# IMUinator2368.net
KiCad netlist of a schematic drawn in EAGLE
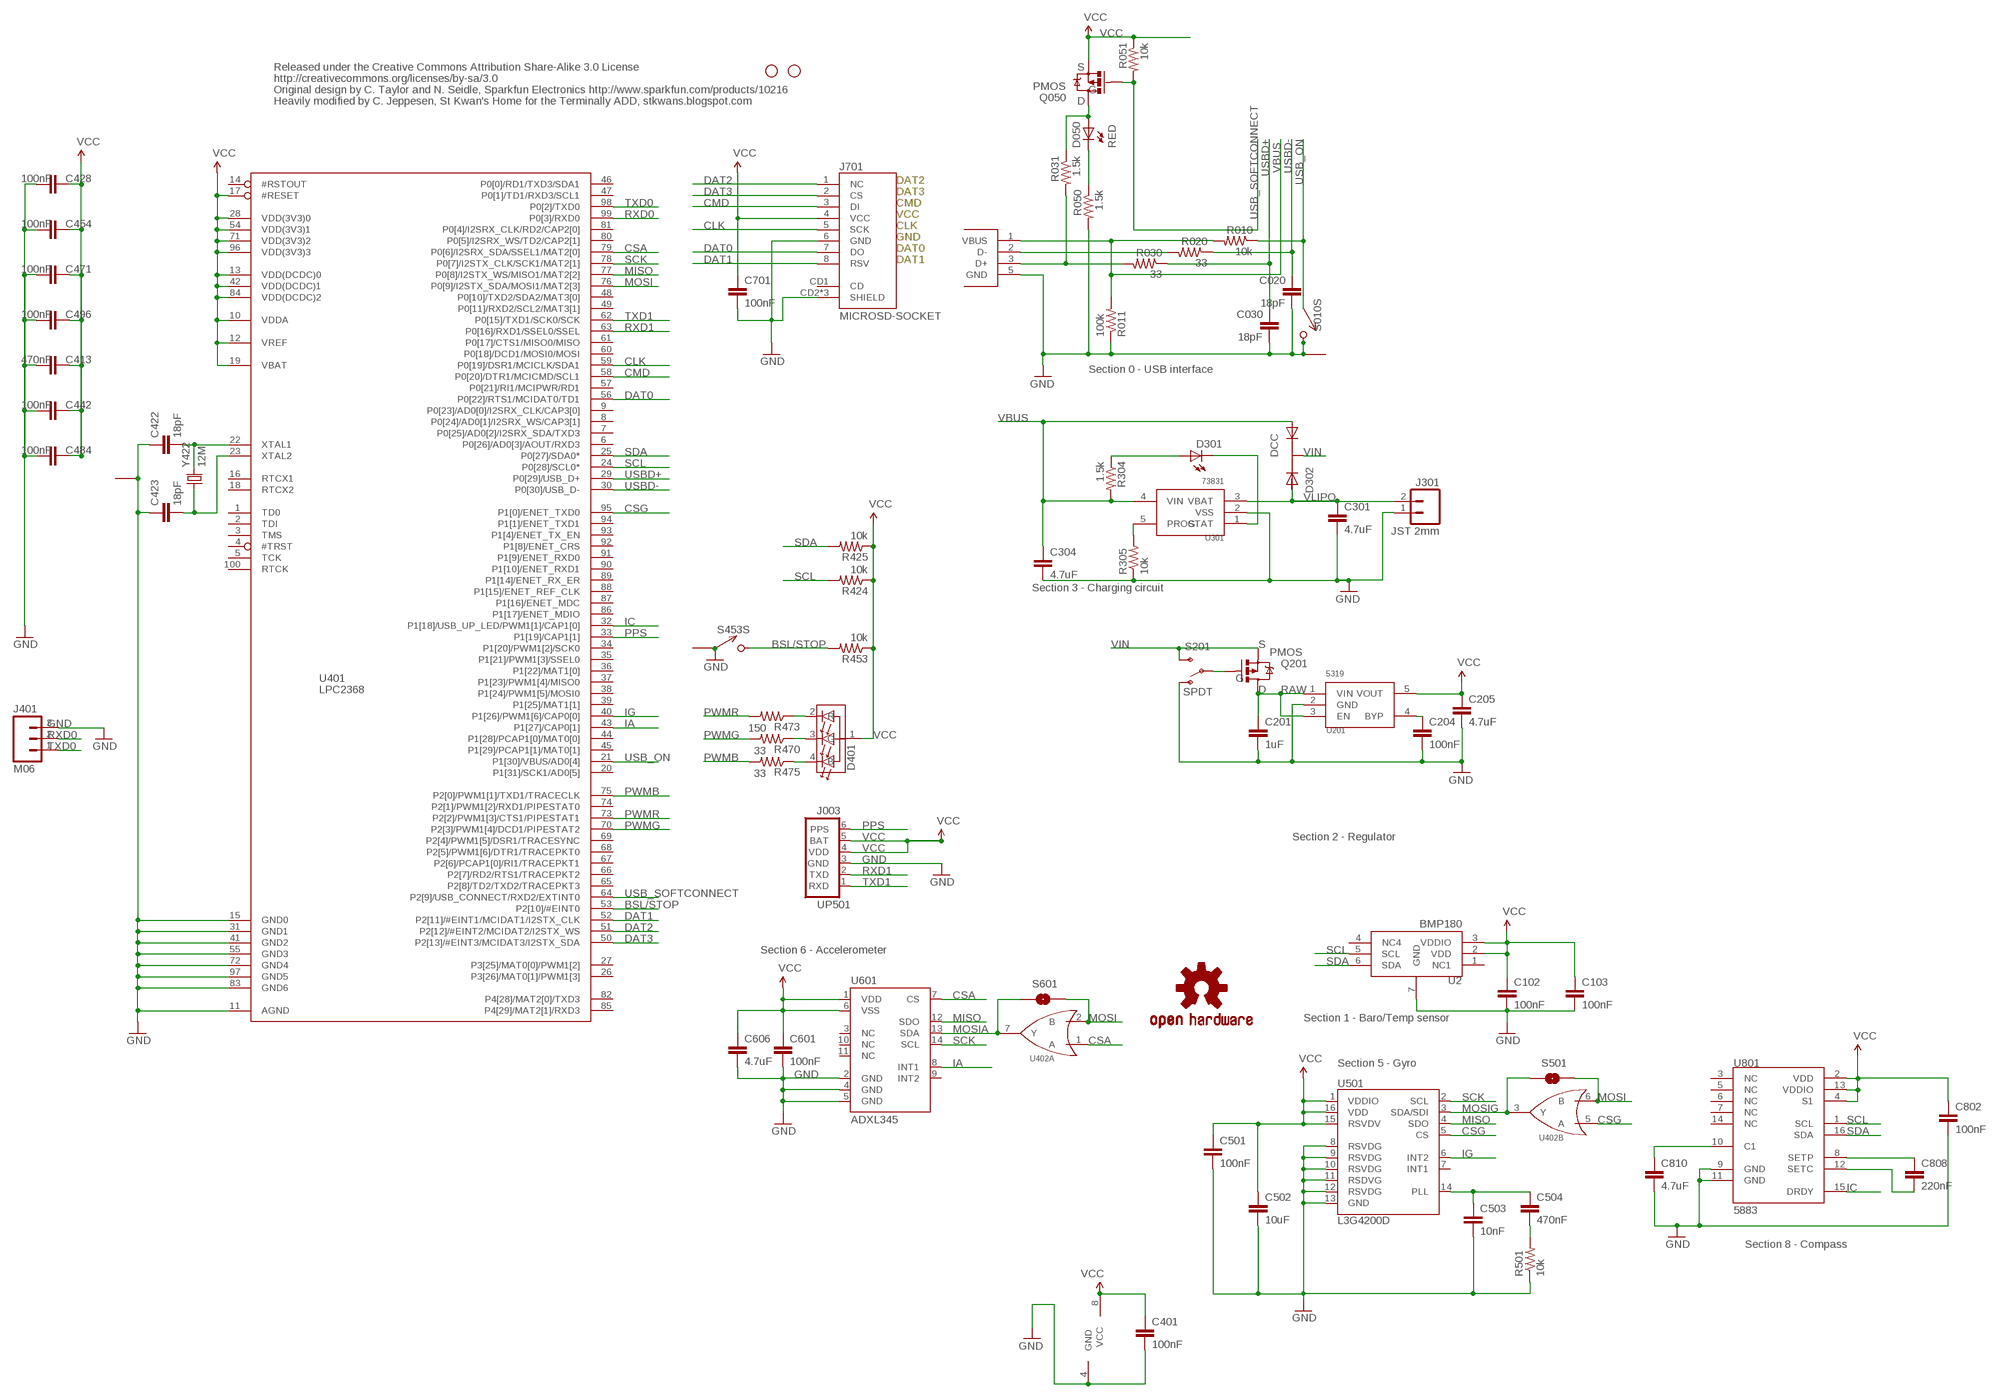
[diagram p0: schematic, sheet 1]

(export (version "E")
  (design (tool "Eeschema 10.0.6"))
  (components
    (comp (ref "C020")
      (value "18pF")
      (footprint "eagle-import:0402-CAP")
      (libsource (lib "eagle-import") (part "CAP0402-CAP"))
    )
    (comp (ref "C030")
      (value "18pF")
      (footprint "eagle-import:0402-CAP")
      (libsource (lib "eagle-import") (part "CAP0402-CAP"))
    )
    (comp (ref "C102")
      (value "100nF")
      (footprint "eagle-import:0402-CAP")
      (libsource (lib "eagle-import") (part "CAP0402-CAP"))
    )
    (comp (ref "C103")
      (value "100nF")
      (footprint "eagle-import:0402-CAP")
      (libsource (lib "eagle-import") (part "CAP0402-CAP"))
    )
    (comp (ref "C201")
      (value "1uF")
      (footprint "eagle-import:0402-CAP")
      (libsource (lib "eagle-import") (part "CAP0402-CAP"))
    )
    (comp (ref "C204")
      (value "100nF")
      (footprint "eagle-import:0402-CAP")
      (libsource (lib "eagle-import") (part "CAP0402-CAP"))
    )
    (comp (ref "C205")
      (value "4.7uF")
      (footprint "eagle-import:0402-CAP")
      (libsource (lib "eagle-import") (part "CAP0402-CAP"))
    )
    (comp (ref "C301")
      (value "4.7uF")
      (footprint "eagle-import:0402-CAP")
      (libsource (lib "eagle-import") (part "CAP0402-CAP"))
    )
    (comp (ref "C304")
      (value "4.7uF")
      (footprint "eagle-import:0402-CAP")
      (libsource (lib "eagle-import") (part "CAP0402-CAP"))
    )
    (comp (ref "C401")
      (value "100nF")
      (footprint "eagle-import:0402-CAP")
      (libsource (lib "eagle-import") (part "CAP0402-CAP"))
    )
    (comp (ref "C413")
      (value "470nF")
      (footprint "eagle-import:0402-CAP")
      (libsource (lib "eagle-import") (part "CAP0402-CAP"))
    )
    (comp (ref "C422")
      (value "18pF")
      (footprint "eagle-import:0402-CAP")
      (libsource (lib "eagle-import") (part "CAP0402-CAP"))
    )
    (comp (ref "C423")
      (value "18pF")
      (footprint "eagle-import:0402-CAP")
      (libsource (lib "eagle-import") (part "CAP0402-CAP"))
    )
    (comp (ref "C428")
      (value "100nF")
      (footprint "eagle-import:0402-CAP")
      (libsource (lib "eagle-import") (part "CAP0402-CAP"))
    )
    (comp (ref "C442")
      (value "100nF")
      (footprint "eagle-import:0402-CAP")
      (libsource (lib "eagle-import") (part "CAP0402-CAP"))
    )
    (comp (ref "C454")
      (value "100nF")
      (footprint "eagle-import:0402-CAP")
      (libsource (lib "eagle-import") (part "CAP0402-CAP"))
    )
    (comp (ref "C471")
      (value "100nF")
      (footprint "eagle-import:0402-CAP")
      (libsource (lib "eagle-import") (part "CAP0402-CAP"))
    )
    (comp (ref "C484")
      (value "100nF")
      (footprint "eagle-import:0402-CAP")
      (libsource (lib "eagle-import") (part "CAP0402-CAP"))
    )
    (comp (ref "C496")
      (value "100nF")
      (footprint "eagle-import:0402-CAP")
      (libsource (lib "eagle-import") (part "CAP0402-CAP"))
    )
    (comp (ref "C501")
      (value "100nF")
      (footprint "eagle-import:0402-CAP")
      (libsource (lib "eagle-import") (part "CAP0402-CAP"))
    )
    (comp (ref "C502")
      (value "10uF")
      (footprint "eagle-import:0603-CAP")
      (libsource (lib "eagle-import") (part "SparkFun-Passives_CAP0603-CAP"))
    )
    (comp (ref "C503")
      (value "10nF")
      (footprint "eagle-import:0402-CAP")
      (libsource (lib "eagle-import") (part "CAP0402-CAP"))
    )
    (comp (ref "C504")
      (value "470nF")
      (footprint "eagle-import:0402-CAP")
      (libsource (lib "eagle-import") (part "CAP0402-CAP"))
    )
    (comp (ref "C601")
      (value "100nF")
      (footprint "eagle-import:0402-CAP")
      (libsource (lib "eagle-import") (part "CAP0402-CAP"))
    )
    (comp (ref "C606")
      (value "4.7uF")
      (footprint "eagle-import:0402-CAP")
      (libsource (lib "eagle-import") (part "CAP0402-CAP"))
    )
    (comp (ref "C701")
      (value "100nF")
      (footprint "eagle-import:0402-CAP")
      (libsource (lib "eagle-import") (part "CAP0402-CAP"))
    )
    (comp (ref "C802")
      (value "100nF")
      (footprint "eagle-import:0402-CAP")
      (libsource (lib "eagle-import") (part "CAP0402-CAP"))
    )
    (comp (ref "C808")
      (value "220nF")
      (footprint "eagle-import:0402-CAP")
      (libsource (lib "eagle-import") (part "CAP0402-CAP"))
    )
    (comp (ref "C810")
      (value "4.7uF")
      (footprint "eagle-import:0402-CAP")
      (libsource (lib "eagle-import") (part "CAP0402-CAP"))
    )
    (comp (ref "D050")
      (value "RED")
      (footprint "eagle-import:LED-0603")
      (libsource (lib "eagle-import") (part "LED0603"))
    )
    (comp (ref "D301")
      (value "RED")
      (footprint "eagle-import:LED-0603")
      (libsource (lib "eagle-import") (part "LED0603"))
    )
    (comp (ref "D302")
      (value "DCC")
      (footprint "eagle-import:SOT-23-3")
      (libsource (lib "eagle-import") (part "PMEG2005CT"))
    )
    (comp (ref "D401")
      (value "RGB")
      (footprint "eagle-import:HSMF-C118")
      (libsource (lib "eagle-import") (part "HSMF-C118"))
    )
    (comp (ref "J001")
      (value "USB_MICROB_JST")
      (footprint "eagle-import:UB-MC5BR3-SD204-4S")
      (libsource (lib "eagle-import") (part "USB_MICROB_JST"))
    )
    (comp (ref "J003")
      (value "UP501")
      (footprint "eagle-import:UP501")
      (libsource (lib "eagle-import") (part "UP501"))
    )
    (comp (ref "J301")
      (value "JST 2mm")
      (footprint "eagle-import:JST-2-SMD")
      (libsource (lib "eagle-import") (part "M02-JST-2MM-SMT"))
    )
    (comp (ref "J401")
      (value "M06")
      (footprint "eagle-import:1X03")
      (libsource (lib "eagle-import") (part "M03PTH"))
    )
    (comp (ref "J701")
      (value "MICROSD-SOCKET")
      (footprint "eagle-import:MICROSD-SOCKET-PP")
      (libsource (lib "eagle-import") (part "MICROSD-SOCKET"))
    )
    (comp (ref "JP1")
      (value "STAND-OFF")
      (footprint "eagle-import:STAND-OFF")
      (libsource (lib "eagle-import") (part "STAND-OFF"))
    )
    (comp (ref "JP2")
      (value "STAND-OFF")
      (footprint "eagle-import:STAND-OFF")
      (libsource (lib "eagle-import") (part "STAND-OFF"))
    )
    (comp (ref "Q050")
      (value "PMOS")
      (footprint "eagle-import:SOT23-3")
      (libsource (lib "eagle-import") (part "MOSFET-PCHANNELSMD"))
    )
    (comp (ref "Q201")
      (value "PMOS")
      (footprint "eagle-import:SOT23-3")
      (libsource (lib "eagle-import") (part "MOSFET-PCHANNELSMD"))
    )
    (comp (ref "R010")
      (value "10k")
      (footprint "eagle-import:0402-RES")
      (libsource (lib "eagle-import") (part "RESISTOR0402-RES"))
    )
    (comp (ref "R011")
      (value "100k")
      (footprint "eagle-import:0402-RES")
      (libsource (lib "eagle-import") (part "RESISTOR0402-RES"))
    )
    (comp (ref "R020")
      (value "33")
      (footprint "eagle-import:0402-RES")
      (libsource (lib "eagle-import") (part "RESISTOR0402-RES"))
    )
    (comp (ref "R030")
      (value "33")
      (footprint "eagle-import:0402-RES")
      (libsource (lib "eagle-import") (part "RESISTOR0402-RES"))
    )
    (comp (ref "R031")
      (value "1.5k")
      (footprint "eagle-import:0402-RES")
      (libsource (lib "eagle-import") (part "RESISTOR0402-RES"))
    )
    (comp (ref "R050")
      (value "1.5k")
      (footprint "eagle-import:0402-RES")
      (libsource (lib "eagle-import") (part "RESISTOR0402-RES"))
    )
    (comp (ref "R051")
      (value "10k")
      (footprint "eagle-import:0402-RES")
      (libsource (lib "eagle-import") (part "RESISTOR0402-RES"))
    )
    (comp (ref "R304")
      (value "1.5k")
      (footprint "eagle-import:0402-RES")
      (libsource (lib "eagle-import") (part "RESISTOR0402-RES"))
    )
    (comp (ref "R305")
      (value "10k")
      (footprint "eagle-import:0402-RES")
      (libsource (lib "eagle-import") (part "RESISTOR0402-RES"))
    )
    (comp (ref "R424")
      (value "10k")
      (footprint "eagle-import:0402-RES")
      (libsource (lib "eagle-import") (part "SparkFun-Passives_RESISTOR0402-RES"))
    )
    (comp (ref "R425")
      (value "10k")
      (footprint "eagle-import:0402-RES")
      (libsource (lib "eagle-import") (part "SparkFun-Passives_RESISTOR0402-RES"))
    )
    (comp (ref "R453")
      (value "10k")
      (footprint "eagle-import:0402-RES")
      (libsource (lib "eagle-import") (part "SparkFun-Passives_RESISTOR0402-RES"))
    )
    (comp (ref "R470")
      (value "33")
      (footprint "eagle-import:0402-RES")
      (libsource (lib "eagle-import") (part "RESISTOR0402-RES"))
    )
    (comp (ref "R473")
      (value "150")
      (footprint "eagle-import:0402-RES")
      (libsource (lib "eagle-import") (part "RESISTOR0402-RES"))
    )
    (comp (ref "R475")
      (value "33")
      (footprint "eagle-import:0402-RES")
      (libsource (lib "eagle-import") (part "RESISTOR0402-RES"))
    )
    (comp (ref "R501")
      (value "10k")
      (footprint "eagle-import:0402-RES")
      (libsource (lib "eagle-import") (part "SparkFun-Passives_RESISTOR0402-RES"))
    )
    (comp (ref "S010")
      (value "SPST")
      (footprint "eagle-import:B3U-1100P")
      (fields (field (name "DIGIKEY") "SW1021CT-ND"))
      (libsource (lib "eagle-import") (part "B3U-1100P"))
    )
    (comp (ref "S201")
      (value "SPDT")
      (footprint "eagle-import:AYZ0202")
      (libsource (lib "eagle-import") (part "SWITCH-SPSTSMD"))
    )
    (comp (ref "S453")
      (value "SPST")
      (footprint "eagle-import:B3U-1100P")
      (fields (field (name "DIGIKEY") "SW1021CT-ND"))
      (libsource (lib "eagle-import") (part "B3U-1100P"))
    )
    (comp (ref "S501")
      (value "SOLDERJUMPERNO")
      (footprint "eagle-import:SJ_2S-NO")
      (libsource (lib "eagle-import") (part "SOLDERJUMPERNO"))
    )
    (comp (ref "S601")
      (value "SOLDERJUMPERNO")
      (footprint "eagle-import:SJ_2S-NO")
      (libsource (lib "eagle-import") (part "SOLDERJUMPERNO"))
    )
    (comp (ref "U$3")
      (value "OSHW-LOGOS")
      (footprint "eagle-import:OSHW-LOGO-S")
      (libsource (lib "eagle-import") (part "OSHW-LOGOS"))
    )
    (comp (ref "U2")
      (value "BMP180")
      (footprint "eagle-import:BMP180")
      (libsource (lib "eagle-import") (part "BMP180"))
    )
    (comp (ref "U201")
      (value "5319")
      (footprint "eagle-import:SOT-23-5")
      (libsource (lib "eagle-import") (part "MIC5319D5"))
    )
    (comp (ref "U301")
      (value "73831")
      (footprint "eagle-import:SOT-23-5")
      (libsource (lib "eagle-import") (part "MCP73831"))
    )
    (comp (ref "U401")
      (value "LPC2368")
      (footprint "eagle-import:LQFP100")
      (libsource (lib "eagle-import") (part "LPC2368"))
    )
    (comp (ref "U402")
      (value "7432")
      (footprint "eagle-import:DCU_8")
      (fields (field (name "DIGIKEY") "296-13268-1-ND"))
      (libsource (lib "eagle-import") (part "SN74LVC2G32"))
    )
    (comp (ref "U501")
      (value "L3G4200D")
      (footprint "eagle-import:LGA16-4X4")
      (libsource (lib "eagle-import") (part "L3G4200D"))
    )
    (comp (ref "U601")
      (value "ADXL345")
      (footprint "eagle-import:LGA14")
      (libsource (lib "eagle-import") (part "ADXL345"))
    )
    (comp (ref "U801")
      (value "5883")
      (footprint "eagle-import:16LPCC")
      (libsource (lib "eagle-import") (part "HMC5883LSMD"))
    )
    (comp (ref "Y422")
      (value "12M")
      (footprint "eagle-import:CRYSTAL_SMD")
      (fields (field (name "DIGIKEY") "887-1316-1-ND"))
      (libsource (lib "eagle-import") (part "TSX-3225"))
    )
  )
  (nets
    (net (code "1") (name "/BSL{slash}STOP") (class "Default")
      (node (ref "R453") (pin "2") (pinfunction "2_2") (pintype "passive"))
      (node (ref "S453") (pin "P$2") (pinfunction "2_P$2") (pintype "bidirectional"))
      (node (ref "U401") (pin "53") (pinfunction "P2[10]/#EINT0_53") (pintype "bidirectional"))
    )
    (net (code "2") (name "/CLK") (class "Default")
      (node (ref "J701") (pin "5") (pinfunction "SCK_5") (pintype "bidirectional"))
      (node (ref "U401") (pin "59") (pinfunction "P0[19]/DSR1/MCICLK/SDA1_59") (pintype "bidirectional"))
    )
    (net (code "3") (name "/CMD") (class "Default")
      (node (ref "J701") (pin "3") (pinfunction "DI_3") (pintype "bidirectional"))
      (node (ref "U401") (pin "58") (pinfunction "P0[20]/DTR1/MCICMD/SCL1_58") (pintype "bidirectional"))
    )
    (net (code "4") (name "/CSA") (class "Default")
      (node (ref "U401") (pin "79") (pinfunction "P0[6]/I2SRX_SDA/SSEL1/MAT2[0]_79") (pintype "bidirectional"))
      (node (ref "U402") (pin "1") (pinfunction "A_1") (pintype "bidirectional"))
      (node (ref "U601") (pin "7") (pinfunction "CS_7") (pintype "bidirectional"))
    )
    (net (code "5") (name "/CSG") (class "Default")
      (node (ref "U401") (pin "95") (pinfunction "P1[0]/ENET_TXD0_95") (pintype "bidirectional"))
      (node (ref "U402") (pin "5") (pinfunction "A_5") (pintype "bidirectional"))
      (node (ref "U501") (pin "5") (pinfunction "CS_5") (pintype "bidirectional"))
    )
    (net (code "6") (name "/DAT0") (class "Default")
      (node (ref "J701") (pin "7") (pinfunction "DO_7") (pintype "bidirectional"))
      (node (ref "U401") (pin "56") (pinfunction "P0[22]/RTS1/MCIDAT0/TD1_56") (pintype "bidirectional"))
    )
    (net (code "7") (name "/DAT1") (class "Default")
      (node (ref "J701") (pin "8") (pinfunction "RSV_8") (pintype "bidirectional"))
      (node (ref "U401") (pin "52") (pinfunction "P2[11]/#EINT1/MCIDAT1/I2STX_CLK_52") (pintype "bidirectional"))
    )
    (net (code "8") (name "/DAT2") (class "Default")
      (node (ref "J701") (pin "1") (pinfunction "NC_1") (pintype "bidirectional"))
      (node (ref "U401") (pin "51") (pinfunction "P2[12]/#EINT2/MCIDAT2/I2STX_WS_51") (pintype "bidirectional"))
    )
    (net (code "9") (name "/DAT3") (class "Default")
      (node (ref "J701") (pin "2") (pinfunction "CS_2") (pintype "bidirectional"))
      (node (ref "U401") (pin "50") (pinfunction "P2[13]/#EINT3/MCIDAT3/I2STX_SDA_50") (pintype "bidirectional"))
    )
    (net (code "10") (name "/IA") (class "Default")
      (node (ref "U401") (pin "43") (pinfunction "P1[27]/CAP0[1]_43") (pintype "bidirectional"))
      (node (ref "U601") (pin "8") (pinfunction "INT1_8") (pintype "bidirectional"))
    )
    (net (code "11") (name "/IC") (class "Default")
      (node (ref "U401") (pin "32") (pinfunction "P1[18]/USB_UP_LED/PWM1[1]/CAP1[0]_32") (pintype "bidirectional"))
      (node (ref "U801") (pin "15") (pinfunction "DRDY_15") (pintype "bidirectional"))
    )
    (net (code "12") (name "/IG") (class "Default")
      (node (ref "U401") (pin "40") (pinfunction "P1[26]/PWM1[6]/CAP0[0]_40") (pintype "bidirectional"))
      (node (ref "U501") (pin "6") (pinfunction "INT2_6") (pintype "bidirectional"))
    )
    (net (code "13") (name "/MISO") (class "Default")
      (node (ref "U401") (pin "77") (pinfunction "P0[8]/I2STX_WS/MISO1/MAT2[2]_77") (pintype "bidirectional"))
      (node (ref "U501") (pin "4") (pinfunction "SDO_4") (pintype "bidirectional"))
      (node (ref "U601") (pin "12") (pinfunction "SDO_12") (pintype "bidirectional"))
    )
    (net (code "14") (name "/MOSI") (class "Default")
      (node (ref "S501") (pin "2") (pinfunction "2_2") (pintype "passive"))
      (node (ref "S601") (pin "2") (pinfunction "2_2") (pintype "passive"))
      (node (ref "U401") (pin "76") (pinfunction "P0[9]/I2STX_SDA/MOSI1/MAT2[3]_76") (pintype "bidirectional"))
      (node (ref "U402") (pin "2") (pinfunction "B_2") (pintype "bidirectional"))
      (node (ref "U402") (pin "6") (pinfunction "B_6") (pintype "bidirectional"))
    )
    (net (code "15") (name "/MOSIA") (class "Default")
      (node (ref "S601") (pin "1") (pinfunction "1_1") (pintype "passive"))
      (node (ref "U402") (pin "7") (pinfunction "Y_7") (pintype "bidirectional"))
      (node (ref "U601") (pin "13") (pinfunction "SDA_13") (pintype "bidirectional"))
    )
    (net (code "16") (name "/MOSIG") (class "Default")
      (node (ref "S501") (pin "1") (pinfunction "1_1") (pintype "passive"))
      (node (ref "U402") (pin "3") (pinfunction "Y_3") (pintype "bidirectional"))
      (node (ref "U501") (pin "3") (pinfunction "SDA/SDI_3") (pintype "bidirectional"))
    )
    (net (code "17") (name "/PPS") (class "Default")
      (node (ref "J003") (pin "6") (pinfunction "PPS_6") (pintype "passive"))
      (node (ref "U401") (pin "33") (pinfunction "P1[19]/CAP1[1]_33") (pintype "bidirectional"))
    )
    (net (code "18") (name "/PWMB") (class "Default")
      (node (ref "R475") (pin "2") (pinfunction "2_2") (pintype "passive"))
      (node (ref "U401") (pin "75") (pinfunction "P2[0]/PWM1[1]/TXD1/TRACECLK_75") (pintype "bidirectional"))
    )
    (net (code "19") (name "/PWMG") (class "Default")
      (node (ref "R470") (pin "2") (pinfunction "2_2") (pintype "passive"))
      (node (ref "U401") (pin "70") (pinfunction "P2[3]/PWM1[4]/DCD1/PIPESTAT2_70") (pintype "bidirectional"))
    )
    (net (code "20") (name "/PWMR") (class "Default")
      (node (ref "R473") (pin "2") (pinfunction "2_2") (pintype "passive"))
      (node (ref "U401") (pin "73") (pinfunction "P2[2]/PWM1[3]/CTS1/PIPESTAT1_73") (pintype "bidirectional"))
    )
    (net (code "21") (name "/RAW") (class "Default")
      (node (ref "C201") (pin "1") (pinfunction "1_1") (pintype "passive"))
      (node (ref "Q201") (pin "3") (pinfunction "D_3") (pintype "passive"))
      (node (ref "U201") (pin "1") (pinfunction "VIN_1") (pintype "bidirectional"))
      (node (ref "U201") (pin "3") (pinfunction "EN_3") (pintype "bidirectional"))
    )
    (net (code "22") (name "/RXD0") (class "Default")
      (node (ref "J401") (pin "2") (pinfunction "2_2") (pintype "passive"))
      (node (ref "U401") (pin "99") (pinfunction "P0[3]/RXD0_99") (pintype "bidirectional"))
    )
    (net (code "23") (name "/RXD1") (class "Default")
      (node (ref "J003") (pin "2") (pinfunction "TXD_2") (pintype "passive"))
      (node (ref "U401") (pin "63") (pinfunction "P0[16]/RXD1/SSEL0/SSEL_63") (pintype "bidirectional"))
    )
    (net (code "24") (name "/SCK") (class "Default")
      (node (ref "U401") (pin "78") (pinfunction "P0[7]/I2STX_CLK/SCK1/MAT2[1]_78") (pintype "bidirectional"))
      (node (ref "U501") (pin "2") (pinfunction "SCL_2") (pintype "bidirectional"))
      (node (ref "U601") (pin "14") (pinfunction "SCL_14") (pintype "bidirectional"))
    )
    (net (code "25") (name "/SCL") (class "Default")
      (node (ref "R424") (pin "2") (pinfunction "2_2") (pintype "passive"))
      (node (ref "U2") (pin "5") (pinfunction "SCL_5") (pintype "input"))
      (node (ref "U401") (pin "24") (pinfunction "P0[28]/SCL0*_24") (pintype "bidirectional"))
      (node (ref "U801") (pin "1") (pinfunction "SCL_1") (pintype "bidirectional"))
    )
    (net (code "26") (name "/SDA") (class "Default")
      (node (ref "R425") (pin "2") (pinfunction "2_2") (pintype "passive"))
      (node (ref "U2") (pin "6") (pinfunction "SDA_6") (pintype "bidirectional"))
      (node (ref "U401") (pin "25") (pinfunction "P0[27]/SDA0*_25") (pintype "bidirectional"))
      (node (ref "U801") (pin "16") (pinfunction "SDA_16") (pintype "bidirectional"))
    )
    (net (code "27") (name "/TXD0") (class "Default")
      (node (ref "J401") (pin "1") (pinfunction "1_1") (pintype "passive"))
      (node (ref "U401") (pin "98") (pinfunction "P0[2]/TXD0_98") (pintype "bidirectional"))
    )
    (net (code "28") (name "/TXD1") (class "Default")
      (node (ref "J003") (pin "1") (pinfunction "RXD_1") (pintype "passive"))
      (node (ref "U401") (pin "62") (pinfunction "P0[15]/TXD1/SCK0/SCK_62") (pintype "bidirectional"))
    )
    (net (code "29") (name "/USBD+") (class "Default")
      (node (ref "C030") (pin "1") (pinfunction "1_1") (pintype "passive"))
      (node (ref "R030") (pin "1") (pinfunction "1_1") (pintype "passive"))
      (node (ref "U401") (pin "29") (pinfunction "P0[29]/USB_D+_29") (pintype "bidirectional"))
    )
    (net (code "30") (name "/USBD-") (class "Default")
      (node (ref "C020") (pin "1") (pinfunction "1_1") (pintype "passive"))
      (node (ref "R020") (pin "1") (pinfunction "1_1") (pintype "passive"))
      (node (ref "U401") (pin "30") (pinfunction "P0[30]/USB_D-_30") (pintype "bidirectional"))
    )
    (net (code "31") (name "/USB_ON") (class "Default")
      (node (ref "R010") (pin "1") (pinfunction "1_1") (pintype "passive"))
      (node (ref "S010") (pin "P$1") (pinfunction "1_P$1") (pintype "bidirectional"))
      (node (ref "U401") (pin "21") (pinfunction "P1[30]/VBUS/AD0[4]_21") (pintype "bidirectional"))
    )
    (net (code "32") (name "/USB_SOFTCONNECT") (class "Default")
      (node (ref "Q050") (pin "1") (pinfunction "G_1") (pintype "passive"))
      (node (ref "R051") (pin "2") (pinfunction "2_2") (pintype "passive"))
      (node (ref "U401") (pin "64") (pinfunction "P2[9]/USB_CONNECT/RXD2/EXTINT0_64") (pintype "bidirectional"))
    )
    (net (code "33") (name "/VBUS") (class "Default")
      (node (ref "C304") (pin "1") (pinfunction "1_1") (pintype "passive"))
      (node (ref "D302") (pin "1") (pinfunction "A1_1") (pintype "passive"))
      (node (ref "J001") (pin "1") (pinfunction "VBUS_1") (pintype "bidirectional"))
      (node (ref "R010") (pin "2") (pinfunction "2_2") (pintype "passive"))
      (node (ref "R011") (pin "2") (pinfunction "2_2") (pintype "passive"))
      (node (ref "R304") (pin "2") (pinfunction "2_2") (pintype "passive"))
      (node (ref "U301") (pin "4") (pinfunction "VIN_4") (pintype "bidirectional"))
    )
    (net (code "34") (name "/VIN") (class "Default")
      (node (ref "D302") (pin "3") (pinfunction "K_3") (pintype "passive"))
      (node (ref "Q201") (pin "2") (pinfunction "S_2") (pintype "passive"))
      (node (ref "S201") (pin "3") (pinfunction "S_3") (pintype "passive"))
    )
    (net (code "35") (name "/VLIPO") (class "Default")
      (node (ref "C301") (pin "1") (pinfunction "1_1") (pintype "passive"))
      (node (ref "D302") (pin "2") (pinfunction "A2_2") (pintype "passive"))
      (node (ref "J301") (pin "2") (pinfunction "2_2") (pintype "passive"))
      (node (ref "U301") (pin "3") (pinfunction "VBAT_3") (pintype "bidirectional"))
    )
    (net (code "36") (name "GND") (class "Default")
      (node (ref "C020") (pin "2") (pinfunction "2_2") (pintype "passive"))
      (node (ref "C030") (pin "2") (pinfunction "2_2") (pintype "passive"))
      (node (ref "C102") (pin "2") (pinfunction "2_2") (pintype "passive"))
      (node (ref "C103") (pin "2") (pinfunction "2_2") (pintype "passive"))
      (node (ref "C201") (pin "2") (pinfunction "2_2") (pintype "passive"))
      (node (ref "C204") (pin "2") (pinfunction "2_2") (pintype "passive"))
      (node (ref "C205") (pin "2") (pinfunction "2_2") (pintype "passive"))
      (node (ref "C301") (pin "2") (pinfunction "2_2") (pintype "passive"))
      (node (ref "C304") (pin "2") (pinfunction "2_2") (pintype "passive"))
      (node (ref "C401") (pin "2") (pinfunction "2_2") (pintype "passive"))
      (node (ref "C413") (pin "2") (pinfunction "2_2") (pintype "passive"))
      (node (ref "C422") (pin "1") (pinfunction "1_1") (pintype "passive"))
      (node (ref "C423") (pin "1") (pinfunction "1_1") (pintype "passive"))
      (node (ref "C428") (pin "2") (pinfunction "2_2") (pintype "passive"))
      (node (ref "C442") (pin "2") (pinfunction "2_2") (pintype "passive"))
      (node (ref "C454") (pin "2") (pinfunction "2_2") (pintype "passive"))
      (node (ref "C471") (pin "2") (pinfunction "2_2") (pintype "passive"))
      (node (ref "C484") (pin "2") (pinfunction "2_2") (pintype "passive"))
      (node (ref "C496") (pin "2") (pinfunction "2_2") (pintype "passive"))
      (node (ref "C501") (pin "2") (pinfunction "2_2") (pintype "passive"))
      (node (ref "C502") (pin "2") (pinfunction "2_2") (pintype "passive"))
      (node (ref "C503") (pin "2") (pinfunction "2_2") (pintype "passive"))
      (node (ref "C601") (pin "2") (pinfunction "2_2") (pintype "passive"))
      (node (ref "C606") (pin "2") (pinfunction "2_2") (pintype "passive"))
      (node (ref "C701") (pin "2") (pinfunction "2_2") (pintype "passive"))
      (node (ref "C802") (pin "2") (pinfunction "2_2") (pintype "passive"))
      (node (ref "C810") (pin "2") (pinfunction "2_2") (pintype "passive"))
      (node (ref "J001") (pin "5") (pinfunction "GND_5") (pintype "bidirectional"))
      (node (ref "J003") (pin "3") (pinfunction "GND_3") (pintype "passive"))
      (node (ref "J301") (pin "1") (pinfunction "1_1") (pintype "passive"))
      (node (ref "J401") (pin "3") (pinfunction "3_3") (pintype "passive"))
      (node (ref "J701") (pin "6") (pinfunction "GND_6") (pintype "bidirectional"))
      (node (ref "J701") (pin "CD2") (pinfunction "SHIELD_CD2") (pintype "bidirectional"))
      (node (ref "J701") (pin "GND1") (pinfunction "SHIELD_GND1") (pintype "bidirectional"))
      (node (ref "J701") (pin "GND3") (pinfunction "SHIELD_GND3") (pintype "bidirectional"))
      (node (ref "R011") (pin "1") (pinfunction "1_1") (pintype "passive"))
      (node (ref "R050") (pin "2") (pinfunction "2_2") (pintype "passive"))
      (node (ref "R305") (pin "1") (pinfunction "1_1") (pintype "passive"))
      (node (ref "R501") (pin "1") (pinfunction "1_1") (pintype "passive"))
      (node (ref "S010") (pin "P$2") (pinfunction "2_P$2") (pintype "bidirectional"))
      (node (ref "S010") (pin "P$3") (pinfunction "1_P$3") (pintype "bidirectional"))
      (node (ref "S201") (pin "1") (pinfunction "O_1") (pintype "passive"))
      (node (ref "S453") (pin "P$1") (pinfunction "1_P$1") (pintype "bidirectional"))
      (node (ref "S453") (pin "P$3") (pinfunction "1_P$3") (pintype "bidirectional"))
      (node (ref "U2") (pin "7") (pinfunction "GND_7") (pintype "power_in"))
      (node (ref "U201") (pin "2") (pinfunction "GND_2") (pintype "bidirectional"))
      (node (ref "U301") (pin "2") (pinfunction "VSS_2") (pintype "bidirectional"))
      (node (ref "U401") (pin "11") (pinfunction "AGND_11") (pintype "bidirectional"))
      (node (ref "U401") (pin "15") (pinfunction "GND0_15") (pintype "bidirectional"))
      (node (ref "U401") (pin "31") (pinfunction "GND1_31") (pintype "bidirectional"))
      (node (ref "U401") (pin "41") (pinfunction "GND2_41") (pintype "bidirectional"))
      (node (ref "U401") (pin "55") (pinfunction "GND3_55") (pintype "bidirectional"))
      (node (ref "U401") (pin "72") (pinfunction "GND4_72") (pintype "bidirectional"))
      (node (ref "U401") (pin "83") (pinfunction "GND6_83") (pintype "bidirectional"))
      (node (ref "U401") (pin "97") (pinfunction "GND5_97") (pintype "bidirectional"))
      (node (ref "U402") (pin "4") (pinfunction "GND_4") (pintype "bidirectional"))
      (node (ref "U501") (pin "10") (pinfunction "RSVDG_10") (pintype "bidirectional"))
      (node (ref "U501") (pin "11") (pinfunction "RSDVG_11") (pintype "bidirectional"))
      (node (ref "U501") (pin "12") (pinfunction "RSVDG_12") (pintype "bidirectional"))
      (node (ref "U501") (pin "13") (pinfunction "GND_13") (pintype "bidirectional"))
      (node (ref "U501") (pin "8") (pinfunction "RSVDG_8") (pintype "bidirectional"))
      (node (ref "U501") (pin "9") (pinfunction "RSVDG_9") (pintype "bidirectional"))
      (node (ref "U601") (pin "2") (pinfunction "GND_2") (pintype "bidirectional"))
      (node (ref "U601") (pin "4") (pinfunction "GND_4") (pintype "bidirectional"))
      (node (ref "U601") (pin "5") (pinfunction "GND_5") (pintype "bidirectional"))
      (node (ref "U801") (pin "11") (pinfunction "GND_11") (pintype "bidirectional"))
      (node (ref "U801") (pin "9") (pinfunction "GND_9") (pintype "bidirectional"))
      (node (ref "Y422") (pin "2") (pinfunction "1_2") (pintype "bidirectional"))
    )
    (net (code "37") (name "Net-(C504-Pad2)") (class "Default")
      (node (ref "C504") (pin "2") (pinfunction "2_2") (pintype "passive"))
      (node (ref "R501") (pin "2") (pinfunction "2_2") (pintype "passive"))
    )
    (net (code "38") (name "Net-(D050-PadC)") (class "Default")
      (node (ref "D050") (pin "C") (pinfunction "C_C") (pintype "passive"))
      (node (ref "R050") (pin "1") (pinfunction "1_1") (pintype "passive"))
    )
    (net (code "39") (name "Net-(D301-PadA)") (class "Default")
      (node (ref "D301") (pin "A") (pinfunction "A_A") (pintype "passive"))
      (node (ref "R304") (pin "1") (pinfunction "1_1") (pintype "passive"))
    )
    (net (code "40") (name "Net-(D401-B)") (class "Default")
      (node (ref "D401") (pin "4") (pinfunction "B_4") (pintype "passive"))
      (node (ref "R475") (pin "1") (pinfunction "1_1") (pintype "passive"))
    )
    (net (code "41") (name "Net-(D401-G)") (class "Default")
      (node (ref "D401") (pin "3") (pinfunction "G_3") (pintype "passive"))
      (node (ref "R470") (pin "1") (pinfunction "1_1") (pintype "passive"))
    )
    (net (code "42") (name "Net-(D401-R)") (class "Default")
      (node (ref "D401") (pin "2") (pinfunction "R_2") (pintype "passive"))
      (node (ref "R473") (pin "1") (pinfunction "1_1") (pintype "passive"))
    )
    (net (code "43") (name "Net-(J001-D+)") (class "Default")
      (node (ref "J001") (pin "3") (pinfunction "D+_3") (pintype "bidirectional"))
      (node (ref "R030") (pin "2") (pinfunction "2_2") (pintype "passive"))
      (node (ref "R031") (pin "2") (pinfunction "2_2") (pintype "passive"))
    )
    (net (code "44") (name "Net-(J001-D-)") (class "Default")
      (node (ref "J001") (pin "2") (pinfunction "D-_2") (pintype "bidirectional"))
      (node (ref "R020") (pin "2") (pinfunction "2_2") (pintype "passive"))
    )
    (net (code "45") (name "Net-(Q050-D)") (class "Default")
      (node (ref "D050") (pin "A") (pinfunction "A_A") (pintype "passive"))
      (node (ref "Q050") (pin "3") (pinfunction "D_3") (pintype "passive"))
      (node (ref "R031") (pin "1") (pinfunction "1_1") (pintype "passive"))
    )
    (net (code "46") (name "Net-(Q201-G)") (class "Default")
      (node (ref "Q201") (pin "1") (pinfunction "G_1") (pintype "passive"))
      (node (ref "S201") (pin "2") (pinfunction "P_2") (pintype "passive"))
    )
    (net (code "47") (name "Net-(U201-BYP)") (class "Default")
      (node (ref "C204") (pin "1") (pinfunction "1_1") (pintype "passive"))
      (node (ref "U201") (pin "4") (pinfunction "BYP_4") (pintype "bidirectional"))
    )
    (net (code "48") (name "Net-(U301-PROG)") (class "Default")
      (node (ref "R305") (pin "2") (pinfunction "2_2") (pintype "passive"))
      (node (ref "U301") (pin "5") (pinfunction "PROG_5") (pintype "bidirectional"))
    )
    (net (code "49") (name "Net-(U301-STAT)") (class "Default")
      (node (ref "D301") (pin "C") (pinfunction "C_C") (pintype "passive"))
      (node (ref "U301") (pin "1") (pinfunction "STAT_1") (pintype "bidirectional"))
    )
    (net (code "50") (name "Net-(U401-XTAL1)") (class "Default")
      (node (ref "C422") (pin "2") (pinfunction "2_2") (pintype "passive"))
      (node (ref "U401") (pin "22") (pinfunction "XTAL1_22") (pintype "bidirectional"))
      (node (ref "Y422") (pin "3") (pinfunction "2_3") (pintype "passive"))
    )
    (net (code "51") (name "Net-(U401-XTAL2)") (class "Default")
      (node (ref "C423") (pin "2") (pinfunction "2_2") (pintype "passive"))
      (node (ref "U401") (pin "23") (pinfunction "XTAL2_23") (pintype "bidirectional"))
      (node (ref "Y422") (pin "1") (pinfunction "1_1") (pintype "passive"))
    )
    (net (code "52") (name "Net-(U501-PLL)") (class "Default")
      (node (ref "C503") (pin "1") (pinfunction "1_1") (pintype "passive"))
      (node (ref "C504") (pin "1") (pinfunction "1_1") (pintype "passive"))
      (node (ref "U501") (pin "14") (pinfunction "PLL_14") (pintype "bidirectional"))
    )
    (net (code "53") (name "Net-(U801-C1)") (class "Default")
      (node (ref "C810") (pin "1") (pinfunction "1_1") (pintype "passive"))
      (node (ref "U801") (pin "10") (pinfunction "C1_10") (pintype "bidirectional"))
    )
    (net (code "54") (name "Net-(U801-SETC)") (class "Default")
      (node (ref "C808") (pin "2") (pinfunction "2_2") (pintype "passive"))
      (node (ref "U801") (pin "12") (pinfunction "SETC_12") (pintype "bidirectional"))
    )
    (net (code "55") (name "Net-(U801-SETP)") (class "Default")
      (node (ref "C808") (pin "1") (pinfunction "1_1") (pintype "passive"))
      (node (ref "U801") (pin "8") (pinfunction "SETP_8") (pintype "bidirectional"))
    )
    (net (code "56") (name "VCC") (class "Default")
      (node (ref "C102") (pin "1") (pinfunction "1_1") (pintype "passive"))
      (node (ref "C103") (pin "1") (pinfunction "1_1") (pintype "passive"))
      (node (ref "C205") (pin "1") (pinfunction "1_1") (pintype "passive"))
      (node (ref "C401") (pin "1") (pinfunction "1_1") (pintype "passive"))
      (node (ref "C413") (pin "1") (pinfunction "1_1") (pintype "passive"))
      (node (ref "C428") (pin "1") (pinfunction "1_1") (pintype "passive"))
      (node (ref "C442") (pin "1") (pinfunction "1_1") (pintype "passive"))
      (node (ref "C454") (pin "1") (pinfunction "1_1") (pintype "passive"))
      (node (ref "C471") (pin "1") (pinfunction "1_1") (pintype "passive"))
      (node (ref "C484") (pin "1") (pinfunction "1_1") (pintype "passive"))
      (node (ref "C496") (pin "1") (pinfunction "1_1") (pintype "passive"))
      (node (ref "C501") (pin "1") (pinfunction "1_1") (pintype "passive"))
      (node (ref "C502") (pin "1") (pinfunction "1_1") (pintype "passive"))
      (node (ref "C601") (pin "1") (pinfunction "1_1") (pintype "passive"))
      (node (ref "C606") (pin "1") (pinfunction "1_1") (pintype "passive"))
      (node (ref "C701") (pin "1") (pinfunction "1_1") (pintype "passive"))
      (node (ref "C802") (pin "1") (pinfunction "1_1") (pintype "passive"))
      (node (ref "D401") (pin "1") (pinfunction "A_1") (pintype "passive"))
      (node (ref "J003") (pin "4") (pinfunction "VDD_4") (pintype "passive"))
      (node (ref "J003") (pin "5") (pinfunction "BAT_5") (pintype "passive"))
      (node (ref "J701") (pin "4") (pinfunction "VCC_4") (pintype "bidirectional"))
      (node (ref "Q050") (pin "2") (pinfunction "S_2") (pintype "passive"))
      (node (ref "R051") (pin "1") (pinfunction "1_1") (pintype "passive"))
      (node (ref "R424") (pin "1") (pinfunction "1_1") (pintype "passive"))
      (node (ref "R425") (pin "1") (pinfunction "1_1") (pintype "passive"))
      (node (ref "R453") (pin "1") (pinfunction "1_1") (pintype "passive"))
      (node (ref "U2") (pin "2") (pinfunction "VDD_2") (pintype "power_in"))
      (node (ref "U2") (pin "3") (pinfunction "VDDIO_3") (pintype "power_in"))
      (node (ref "U201") (pin "5") (pinfunction "VOUT_5") (pintype "bidirectional"))
      (node (ref "U401") (pin "10") (pinfunction "VDDA_10") (pintype "bidirectional"))
      (node (ref "U401") (pin "12") (pinfunction "VREF_12") (pintype "bidirectional"))
      (node (ref "U401") (pin "13") (pinfunction "VDD(DCDC)0_13") (pintype "bidirectional"))
      (node (ref "U401") (pin "17") (pinfunction "#RESET_17") (pintype "bidirectional"))
      (node (ref "U401") (pin "19") (pinfunction "VBAT_19") (pintype "bidirectional"))
      (node (ref "U401") (pin "28") (pinfunction "VDD(3V3)0_28") (pintype "bidirectional"))
      (node (ref "U401") (pin "42") (pinfunction "VDD(DCDC)1_42") (pintype "bidirectional"))
      (node (ref "U401") (pin "54") (pinfunction "VDD(3V3)1_54") (pintype "bidirectional"))
      (node (ref "U401") (pin "71") (pinfunction "VDD(3V3)2_71") (pintype "bidirectional"))
      (node (ref "U401") (pin "84") (pinfunction "VDD(DCDC)2_84") (pintype "bidirectional"))
      (node (ref "U401") (pin "96") (pinfunction "VDD(3V3)3_96") (pintype "bidirectional"))
      (node (ref "U402") (pin "8") (pinfunction "VCC_8") (pintype "bidirectional"))
      (node (ref "U501") (pin "1") (pinfunction "VDDIO_1") (pintype "bidirectional"))
      (node (ref "U501") (pin "15") (pinfunction "RSVDV_15") (pintype "bidirectional"))
      (node (ref "U501") (pin "16") (pinfunction "VDD_16") (pintype "bidirectional"))
      (node (ref "U601") (pin "1") (pinfunction "VDD_1") (pintype "bidirectional"))
      (node (ref "U601") (pin "6") (pinfunction "VSS_6") (pintype "bidirectional"))
      (node (ref "U801") (pin "13") (pinfunction "VDDIO_13") (pintype "bidirectional"))
      (node (ref "U801") (pin "2") (pinfunction "VDD_2") (pintype "bidirectional"))
      (node (ref "U801") (pin "4") (pinfunction "S1_4") (pintype "bidirectional"))
    )
    (net (code "57") (name "unconnected-(J701-CD-PadCD1)") (class "Default")
      (node (ref "J701") (pin "CD1") (pinfunction "CD_CD1") (pintype "bidirectional"))
    )
    (net (code "58") (name "unconnected-(U2-NC1-Pad1)") (class "Default")
      (node (ref "U2") (pin "1") (pinfunction "NC1_1") (pintype "no_connect"))
    )
    (net (code "59") (name "unconnected-(U2-NC4-Pad4)") (class "Default")
      (node (ref "U2") (pin "4") (pinfunction "NC4_4") (pintype "no_connect"))
    )
    (net (code "60") (name "unconnected-(U401-#RSTOUT-Pad14)") (class "Default")
      (node (ref "U401") (pin "14") (pinfunction "#RSTOUT_14") (pintype "bidirectional"))
    )
    (net (code "61") (name "unconnected-(U401-#TRST-Pad4)") (class "Default")
      (node (ref "U401") (pin "4") (pinfunction "#TRST_4") (pintype "bidirectional"))
    )
    (net (code "62") (name "unconnected-(U401-P0[0]{slash}RD1{slash}TXD3{slash}SDA1-Pad46)") (class "Default")
      (node (ref "U401") (pin "46") (pinfunction "P0[0]/RD1/TXD3/SDA1_46") (pintype "bidirectional"))
    )
    (net (code "63") (name "unconnected-(U401-P0[1]{slash}TD1{slash}RXD3{slash}SCL1-Pad47)") (class "Default")
      (node (ref "U401") (pin "47") (pinfunction "P0[1]/TD1/RXD3/SCL1_47") (pintype "bidirectional"))
    )
    (net (code "64") (name "unconnected-(U401-P0[4]{slash}I2SRX_CLK{slash}RD2{slash}CAP2[0]-Pad81)") (class "Default")
      (node (ref "U401") (pin "81") (pinfunction "P0[4]/I2SRX_CLK/RD2/CAP2[0]_81") (pintype "bidirectional"))
    )
    (net (code "65") (name "unconnected-(U401-P0[5]{slash}I2SRX_WS{slash}TD2{slash}CAP2[1]-Pad80)") (class "Default")
      (node (ref "U401") (pin "80") (pinfunction "P0[5]/I2SRX_WS/TD2/CAP2[1]_80") (pintype "bidirectional"))
    )
    (net (code "66") (name "unconnected-(U401-P0[10]{slash}TXD2{slash}SDA2{slash}MAT3[0]-Pad48)") (class "Default")
      (node (ref "U401") (pin "48") (pinfunction "P0[10]/TXD2/SDA2/MAT3[0]_48") (pintype "bidirectional"))
    )
    (net (code "67") (name "unconnected-(U401-P0[11]{slash}RXD2{slash}SCL2{slash}MAT3[1]-Pad49)") (class "Default")
      (node (ref "U401") (pin "49") (pinfunction "P0[11]/RXD2/SCL2/MAT3[1]_49") (pintype "bidirectional"))
    )
    (net (code "68") (name "unconnected-(U401-P0[17]{slash}CTS1{slash}MISO0{slash}MISO-Pad61)") (class "Default")
      (node (ref "U401") (pin "61") (pinfunction "P0[17]/CTS1/MISO0/MISO_61") (pintype "bidirectional"))
    )
    (net (code "69") (name "unconnected-(U401-P0[18]{slash}DCD1{slash}MOSI0{slash}MOSI-Pad60)") (class "Default")
      (node (ref "U401") (pin "60") (pinfunction "P0[18]/DCD1/MOSI0/MOSI_60") (pintype "bidirectional"))
    )
    (net (code "70") (name "unconnected-(U401-P0[21]{slash}RI1{slash}MCIPWR{slash}RD1-Pad57)") (class "Default")
      (node (ref "U401") (pin "57") (pinfunction "P0[21]/RI1/MCIPWR/RD1_57") (pintype "bidirectional"))
    )
    (net (code "71") (name "unconnected-(U401-P0[23]{slash}AD0[0]{slash}I2SRX_CLK{slash}CAP3[0]-Pad9)") (class "Default")
      (node (ref "U401") (pin "9") (pinfunction "P0[23]/AD0[0]/I2SRX_CLK/CAP3[0]_9") (pintype "bidirectional"))
    )
    (net (code "72") (name "unconnected-(U401-P0[24]{slash}AD0[1]{slash}I2SRX_WS{slash}CAP3[1]-Pad8)") (class "Default")
      (node (ref "U401") (pin "8") (pinfunction "P0[24]/AD0[1]/I2SRX_WS/CAP3[1]_8") (pintype "bidirectional"))
    )
    (net (code "73") (name "unconnected-(U401-P0[25]{slash}AD0[2]{slash}I2SRX_SDA{slash}TXD3-Pad7)") (class "Default")
      (node (ref "U401") (pin "7") (pinfunction "P0[25]/AD0[2]/I2SRX_SDA/TXD3_7") (pintype "bidirectional"))
    )
    (net (code "74") (name "unconnected-(U401-P0[26]{slash}AD0[3]{slash}AOUT{slash}RXD3-Pad6)") (class "Default")
      (node (ref "U401") (pin "6") (pinfunction "P0[26]/AD0[3]/AOUT/RXD3_6") (pintype "bidirectional"))
    )
    (net (code "75") (name "unconnected-(U401-P1[1]{slash}ENET_TXD1-Pad94)") (class "Default")
      (node (ref "U401") (pin "94") (pinfunction "P1[1]/ENET_TXD1_94") (pintype "bidirectional"))
    )
    (net (code "76") (name "unconnected-(U401-P1[4]{slash}ENET_TX_EN-Pad93)") (class "Default")
      (node (ref "U401") (pin "93") (pinfunction "P1[4]/ENET_TX_EN_93") (pintype "bidirectional"))
    )
    (net (code "77") (name "unconnected-(U401-P1[8]{slash}ENET_CRS-Pad92)") (class "Default")
      (node (ref "U401") (pin "92") (pinfunction "P1[8]/ENET_CRS_92") (pintype "bidirectional"))
    )
    (net (code "78") (name "unconnected-(U401-P1[9]{slash}ENET_RXD0-Pad91)") (class "Default")
      (node (ref "U401") (pin "91") (pinfunction "P1[9]/ENET_RXD0_91") (pintype "bidirectional"))
    )
    (net (code "79") (name "unconnected-(U401-P1[10]{slash}ENET_RXD1-Pad90)") (class "Default")
      (node (ref "U401") (pin "90") (pinfunction "P1[10]/ENET_RXD1_90") (pintype "bidirectional"))
    )
    (net (code "80") (name "unconnected-(U401-P1[14]{slash}ENET_RX_ER-Pad89)") (class "Default")
      (node (ref "U401") (pin "89") (pinfunction "P1[14]/ENET_RX_ER_89") (pintype "bidirectional"))
    )
    (net (code "81") (name "unconnected-(U401-P1[15]{slash}ENET_REF_CLK-Pad88)") (class "Default")
      (node (ref "U401") (pin "88") (pinfunction "P1[15]/ENET_REF_CLK_88") (pintype "bidirectional"))
    )
    (net (code "82") (name "unconnected-(U401-P1[16]{slash}ENET_MDC-Pad87)") (class "Default")
      (node (ref "U401") (pin "87") (pinfunction "P1[16]/ENET_MDC_87") (pintype "bidirectional"))
    )
    (net (code "83") (name "unconnected-(U401-P1[17]{slash}ENET_MDIO-Pad86)") (class "Default")
      (node (ref "U401") (pin "86") (pinfunction "P1[17]/ENET_MDIO_86") (pintype "bidirectional"))
    )
    (net (code "84") (name "unconnected-(U401-P1[20]{slash}PWM1[2]{slash}SCK0-Pad34)") (class "Default")
      (node (ref "U401") (pin "34") (pinfunction "P1[20]/PWM1[2]/SCK0_34") (pintype "bidirectional"))
    )
    (net (code "85") (name "unconnected-(U401-P1[21]{slash}PWM1[3]{slash}SSEL0-Pad35)") (class "Default")
      (node (ref "U401") (pin "35") (pinfunction "P1[21]/PWM1[3]/SSEL0_35") (pintype "bidirectional"))
    )
    (net (code "86") (name "unconnected-(U401-P1[22]{slash}MAT1[0]-Pad36)") (class "Default")
      (node (ref "U401") (pin "36") (pinfunction "P1[22]/MAT1[0]_36") (pintype "bidirectional"))
    )
    (net (code "87") (name "unconnected-(U401-P1[23]{slash}PWM1[4]{slash}MISO0-Pad37)") (class "Default")
      (node (ref "U401") (pin "37") (pinfunction "P1[23]/PWM1[4]/MISO0_37") (pintype "bidirectional"))
    )
    (net (code "88") (name "unconnected-(U401-P1[24]{slash}PWM1[5]{slash}MOSI0-Pad38)") (class "Default")
      (node (ref "U401") (pin "38") (pinfunction "P1[24]/PWM1[5]/MOSI0_38") (pintype "bidirectional"))
    )
    (net (code "89") (name "unconnected-(U401-P1[25]{slash}MAT1[1]-Pad39)") (class "Default")
      (node (ref "U401") (pin "39") (pinfunction "P1[25]/MAT1[1]_39") (pintype "bidirectional"))
    )
    (net (code "90") (name "unconnected-(U401-P1[28]{slash}PCAP1[0]{slash}MAT0[0]-Pad44)") (class "Default")
      (node (ref "U401") (pin "44") (pinfunction "P1[28]/PCAP1[0]/MAT0[0]_44") (pintype "bidirectional"))
    )
    (net (code "91") (name "unconnected-(U401-P1[29]{slash}PCAP1[1]{slash}MAT0[1]-Pad45)") (class "Default")
      (node (ref "U401") (pin "45") (pinfunction "P1[29]/PCAP1[1]/MAT0[1]_45") (pintype "bidirectional"))
    )
    (net (code "92") (name "unconnected-(U401-P1[31]{slash}SCK1{slash}AD0[5]-Pad20)") (class "Default")
      (node (ref "U401") (pin "20") (pinfunction "P1[31]/SCK1/AD0[5]_20") (pintype "bidirectional"))
    )
    (net (code "93") (name "unconnected-(U401-P2[1]{slash}PWM1[2]{slash}RXD1{slash}PIPESTAT0-Pad74)") (class "Default")
      (node (ref "U401") (pin "74") (pinfunction "P2[1]/PWM1[2]/RXD1/PIPESTAT0_74") (pintype "bidirectional"))
    )
    (net (code "94") (name "unconnected-(U401-P2[4]{slash}PWM1[5]{slash}DSR1{slash}TRACESYNC-Pad69)") (class "Default")
      (node (ref "U401") (pin "69") (pinfunction "P2[4]/PWM1[5]/DSR1/TRACESYNC_69") (pintype "bidirectional"))
    )
    (net (code "95") (name "unconnected-(U401-P2[5]{slash}PWM1[6]{slash}DTR1{slash}TRACEPKT0-Pad68)") (class "Default")
      (node (ref "U401") (pin "68") (pinfunction "P2[5]/PWM1[6]/DTR1/TRACEPKT0_68") (pintype "bidirectional"))
    )
    (net (code "96") (name "unconnected-(U401-P2[6]{slash}PCAP1[0]{slash}RI1{slash}TRACEPKT1-Pad67)") (class "Default")
      (node (ref "U401") (pin "67") (pinfunction "P2[6]/PCAP1[0]/RI1/TRACEPKT1_67") (pintype "bidirectional"))
    )
    (net (code "97") (name "unconnected-(U401-P2[7]{slash}RD2{slash}RTS1{slash}TRACEPKT2-Pad66)") (class "Default")
      (node (ref "U401") (pin "66") (pinfunction "P2[7]/RD2/RTS1/TRACEPKT2_66") (pintype "bidirectional"))
    )
    (net (code "98") (name "unconnected-(U401-P2[8]{slash}TD2{slash}TXD2{slash}TRACEPKT3-Pad65)") (class "Default")
      (node (ref "U401") (pin "65") (pinfunction "P2[8]/TD2/TXD2/TRACEPKT3_65") (pintype "bidirectional"))
    )
    (net (code "99") (name "unconnected-(U401-P3[25]{slash}MAT0[0]{slash}PWM1[2]-Pad27)") (class "Default")
      (node (ref "U401") (pin "27") (pinfunction "P3[25]/MAT0[0]/PWM1[2]_27") (pintype "bidirectional"))
    )
    (net (code "100") (name "unconnected-(U401-P3[26]{slash}MAT0[1]{slash}PWM1[3]-Pad26)") (class "Default")
      (node (ref "U401") (pin "26") (pinfunction "P3[26]/MAT0[1]/PWM1[3]_26") (pintype "bidirectional"))
    )
    (net (code "101") (name "unconnected-(U401-P4[28]{slash}MAT2[0]{slash}TXD3-Pad82)") (class "Default")
      (node (ref "U401") (pin "82") (pinfunction "P4[28]/MAT2[0]/TXD3_82") (pintype "bidirectional"))
    )
    (net (code "102") (name "unconnected-(U401-P4[29]{slash}MAT2[1]{slash}RXD3-Pad85)") (class "Default")
      (node (ref "U401") (pin "85") (pinfunction "P4[29]/MAT2[1]/RXD3_85") (pintype "bidirectional"))
    )
    (net (code "103") (name "unconnected-(U401-RTCK-Pad100)") (class "Default")
      (node (ref "U401") (pin "100") (pinfunction "RTCK_100") (pintype "bidirectional"))
    )
    (net (code "104") (name "unconnected-(U401-RTCX1-Pad16)") (class "Default")
      (node (ref "U401") (pin "16") (pinfunction "RTCX1_16") (pintype "bidirectional"))
    )
    (net (code "105") (name "unconnected-(U401-RTCX2-Pad18)") (class "Default")
      (node (ref "U401") (pin "18") (pinfunction "RTCX2_18") (pintype "bidirectional"))
    )
    (net (code "106") (name "unconnected-(U401-TCK-Pad5)") (class "Default")
      (node (ref "U401") (pin "5") (pinfunction "TCK_5") (pintype "bidirectional"))
    )
    (net (code "107") (name "unconnected-(U401-TD0-Pad1)") (class "Default")
      (node (ref "U401") (pin "1") (pinfunction "TD0_1") (pintype "bidirectional"))
    )
    (net (code "108") (name "unconnected-(U401-TDI-Pad2)") (class "Default")
      (node (ref "U401") (pin "2") (pinfunction "TDI_2") (pintype "bidirectional"))
    )
    (net (code "109") (name "unconnected-(U401-TMS-Pad3)") (class "Default")
      (node (ref "U401") (pin "3") (pinfunction "TMS_3") (pintype "bidirectional"))
    )
    (net (code "110") (name "unconnected-(U501-INT1-Pad7)") (class "Default")
      (node (ref "U501") (pin "7") (pinfunction "INT1_7") (pintype "bidirectional"))
    )
    (net (code "111") (name "unconnected-(U601-INT2-Pad9)") (class "Default")
      (node (ref "U601") (pin "9") (pinfunction "INT2_9") (pintype "bidirectional"))
    )
    (net (code "112") (name "unconnected-(U601-NC-Pad3)") (class "Default")
      (node (ref "U601") (pin "3") (pinfunction "NC_3") (pintype "bidirectional"))
    )
    (net (code "113") (name "unconnected-(U601-NC-Pad10)") (class "Default")
      (node (ref "U601") (pin "10") (pinfunction "NC_10") (pintype "bidirectional"))
    )
    (net (code "114") (name "unconnected-(U601-NC-Pad11)") (class "Default")
      (node (ref "U601") (pin "11") (pinfunction "NC_11") (pintype "bidirectional"))
    )
    (net (code "115") (name "unconnected-(U801-NC-Pad3)") (class "Default")
      (node (ref "U801") (pin "3") (pinfunction "NC_3") (pintype "bidirectional"))
    )
    (net (code "116") (name "unconnected-(U801-NC-Pad5)") (class "Default")
      (node (ref "U801") (pin "5") (pinfunction "NC_5") (pintype "bidirectional"))
    )
    (net (code "117") (name "unconnected-(U801-NC-Pad6)") (class "Default")
      (node (ref "U801") (pin "6") (pinfunction "NC_6") (pintype "bidirectional"))
    )
    (net (code "118") (name "unconnected-(U801-NC-Pad7)") (class "Default")
      (node (ref "U801") (pin "7") (pinfunction "NC_7") (pintype "bidirectional"))
    )
    (net (code "119") (name "unconnected-(U801-NC-Pad14)") (class "Default")
      (node (ref "U801") (pin "14") (pinfunction "NC_14") (pintype "bidirectional"))
    )
  )
)
